# 5VPart.net
KiCad netlist of a schematic drawn in EAGLE
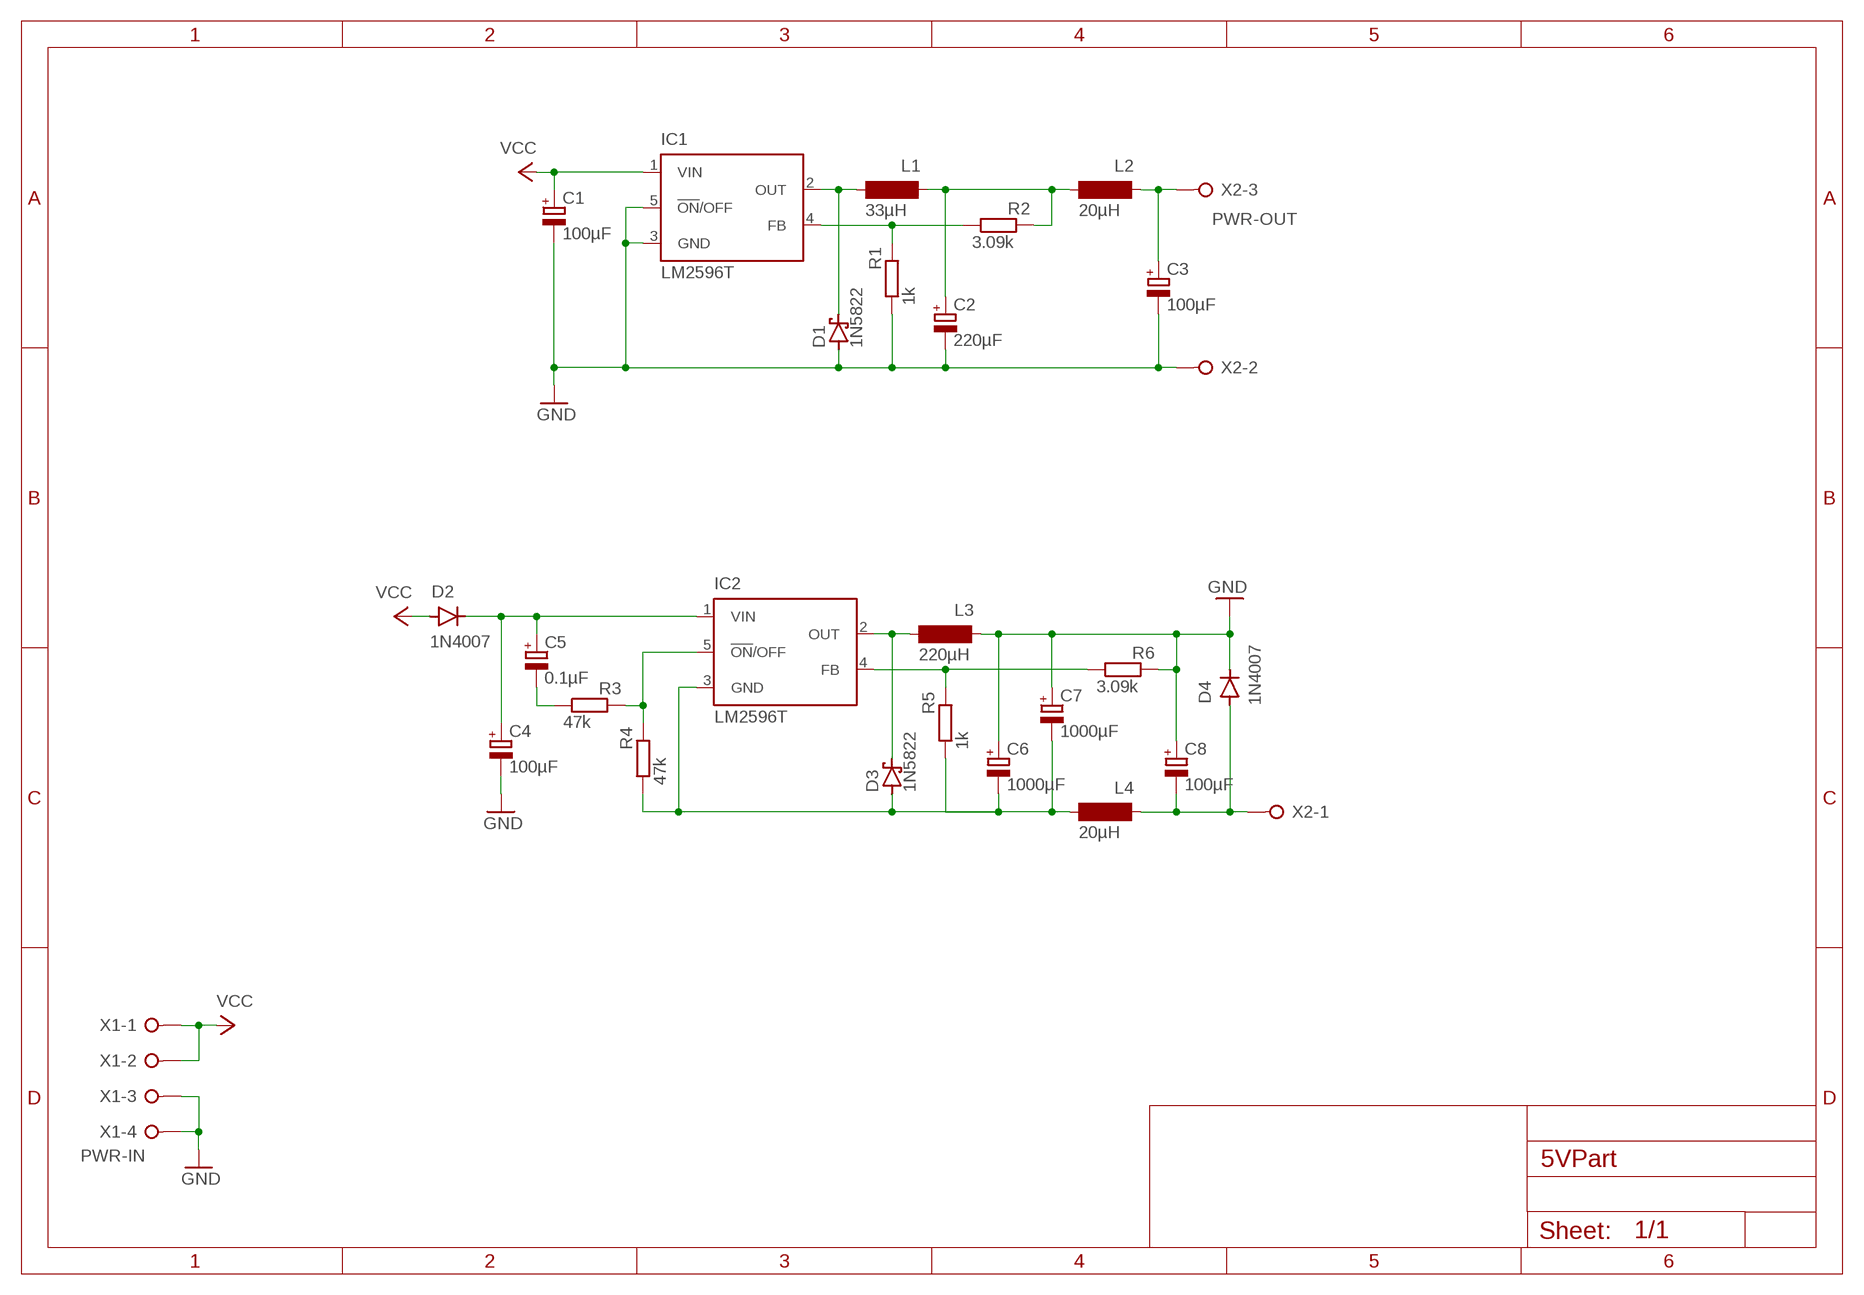
[diagram p0: schematic, sheet 1]

(export (version "E")
  (design (tool "Eeschema 10.0.6"))
  (components
    (comp (ref "C1")
      (value "100µF")
      (footprint "eagle-import:E2,5-6")
      (libsource (lib "eagle-import") (part "CPOL-EUE2.5-6"))
    )
    (comp (ref "C2")
      (value "220µF")
      (footprint "eagle-import:E2,5-6")
      (libsource (lib "eagle-import") (part "CPOL-EUE2.5-6"))
    )
    (comp (ref "C3")
      (value "100µF")
      (footprint "eagle-import:E2,5-6")
      (libsource (lib "eagle-import") (part "CPOL-EUE2.5-6"))
    )
    (comp (ref "C4")
      (value "100µF")
      (footprint "eagle-import:E2,5-6")
      (libsource (lib "eagle-import") (part "CPOL-EUE2.5-6"))
    )
    (comp (ref "C5")
      (value "0.1µF")
      (footprint "eagle-import:E2-4")
      (libsource (lib "eagle-import") (part "CPOL-EUE2-4"))
    )
    (comp (ref "C6")
      (value "1000µF")
      (footprint "eagle-import:E5-10,5")
      (libsource (lib "eagle-import") (part "CPOL-EUE5-10.5"))
    )
    (comp (ref "C7")
      (value "1000µF")
      (footprint "eagle-import:E5-10,5")
      (libsource (lib "eagle-import") (part "CPOL-EUE5-10.5"))
    )
    (comp (ref "C8")
      (value "100µF")
      (footprint "eagle-import:E2,5-6")
      (libsource (lib "eagle-import") (part "CPOL-EUE2.5-6"))
    )
    (comp (ref "D1")
      (value "1N5822")
      (footprint "eagle-import:C4111-15")
      (libsource (lib "eagle-import") (part "1N5908"))
    )
    (comp (ref "D2")
      (value "1N4007")
      (footprint "eagle-import:DO-41")
      (fields
        (field (name "DIGIKEY_PART_NUMBER") "1N4007MSCT-ND")
        (field (name "MANUFACTURER") "Micro Commercial Co")
        (field (name "CREATED_BY") "PCBLayout.com")
      )
      (libsource (lib "eagle-import") (part "1N4007"))
    )
    (comp (ref "D3")
      (value "1N5822")
      (footprint "eagle-import:C4111-15")
      (libsource (lib "eagle-import") (part "1N5908"))
    )
    (comp (ref "D4")
      (value "1N4007")
      (footprint "eagle-import:DO-41")
      (fields
        (field (name "DIGIKEY_PART_NUMBER") "1N4007MSCT-ND")
        (field (name "MANUFACTURER") "Micro Commercial Co")
        (field (name "CREATED_BY") "PCBLayout.com")
      )
      (libsource (lib "eagle-import") (part "1N4007"))
    )
    (comp (ref "IC1")
      (value "LM2596T")
      (footprint "eagle-import:T05D")
      (fields (field (name "MPN") "LM2596T-ADJ/LF02"))
      (libsource (lib "eagle-import") (part "LM2596T"))
    )
    (comp (ref "IC2")
      (value "LM2596T")
      (footprint "eagle-import:T05D")
      (fields (field (name "MPN") "LM2596T-ADJ/LF02"))
      (libsource (lib "eagle-import") (part "LM2596T"))
    )
    (comp (ref "L1")
      (value "33µH")
      (footprint "eagle-import:IND-120")
      (libsource (lib "eagle-import") (part "IND-120-330K"))
    )
    (comp (ref "L2")
      (value "20µH")
      (footprint "eagle-import:B82111B")
      (libsource (lib "eagle-import") (part "B82111B0000C020"))
    )
    (comp (ref "L3")
      (value "220µH")
      (footprint "eagle-import:11PHC")
      (libsource (lib "eagle-import") (part "11PHC-221K-50"))
    )
    (comp (ref "L4")
      (value "20µH")
      (footprint "eagle-import:B82111B")
      (libsource (lib "eagle-import") (part "B82111B0000C020"))
    )
    (comp (ref "R1")
      (value "1k")
      (footprint "eagle-import:0207_10")
      (libsource (lib "eagle-import") (part "R-EU_0207/10"))
    )
    (comp (ref "R2")
      (value "3.09k")
      (footprint "eagle-import:0207_10")
      (libsource (lib "eagle-import") (part "R-EU_0207/10"))
    )
    (comp (ref "R3")
      (value "47k")
      (footprint "eagle-import:0207_10")
      (libsource (lib "eagle-import") (part "R-EU_0207/10"))
    )
    (comp (ref "R4")
      (value "47k")
      (footprint "eagle-import:0207_10")
      (libsource (lib "eagle-import") (part "R-EU_0207/10"))
    )
    (comp (ref "R5")
      (value "1k")
      (footprint "eagle-import:0207_10")
      (libsource (lib "eagle-import") (part "R-EU_0207/10"))
    )
    (comp (ref "R6")
      (value "3.09k")
      (footprint "eagle-import:0207_10")
      (libsource (lib "eagle-import") (part "R-EU_0207/10"))
    )
    (comp (ref "X1")
      (value "PWR-IN")
      (footprint "eagle-import:W237-4P")
      (libsource (lib "eagle-import") (part "W237-04P"))
    )
    (comp (ref "X2")
      (value "PWR-OUT")
      (footprint "eagle-import:W237-133")
      (libsource (lib "eagle-import") (part "W237-03P"))
    )
  )
  (nets
    (net (code "1") (name "GND") (class "Default")
      (node (ref "C1") (pin "-") (pinfunction "-_-") (pintype "passive"))
      (node (ref "C2") (pin "-") (pinfunction "-_-") (pintype "passive"))
      (node (ref "C3") (pin "-") (pinfunction "-_-") (pintype "passive"))
      (node (ref "C4") (pin "-") (pinfunction "-_-") (pintype "passive"))
      (node (ref "C6") (pin "+") (pinfunction "+_+") (pintype "passive"))
      (node (ref "C7") (pin "+") (pinfunction "+_+") (pintype "passive"))
      (node (ref "C8") (pin "+") (pinfunction "+_+") (pintype "passive"))
      (node (ref "D1") (pin "A") (pinfunction "A_A") (pintype "passive"))
      (node (ref "D4") (pin "C") (pinfunction "C_C") (pintype "passive"))
      (node (ref "IC1") (pin "3") (pinfunction "GND_3") (pintype "power_in"))
      (node (ref "IC1") (pin "5") (pinfunction "~{ON}/OFF_5") (pintype "input"))
      (node (ref "L3") (pin "P$2") (pinfunction "2_P$2") (pintype "passive"))
      (node (ref "R1") (pin "1") (pinfunction "1_1") (pintype "passive"))
      (node (ref "R6") (pin "2") (pinfunction "2_2") (pintype "passive"))
      (node (ref "X1") (pin "3") (pinfunction "KL_3") (pintype "passive"))
      (node (ref "X1") (pin "4") (pinfunction "KL_4") (pintype "passive"))
      (node (ref "X2") (pin "2") (pinfunction "KL_2") (pintype "passive"))
    )
    (net (code "2") (name "Net-(C5-Pad-)") (class "Default")
      (node (ref "C5") (pin "-") (pinfunction "-_-") (pintype "passive"))
      (node (ref "R3") (pin "1") (pinfunction "1_1") (pintype "passive"))
    )
    (net (code "3") (name "Net-(IC1-FB)") (class "Default")
      (node (ref "IC1") (pin "4") (pinfunction "FB_4") (pintype "input"))
      (node (ref "R1") (pin "2") (pinfunction "2_2") (pintype "passive"))
      (node (ref "R2") (pin "1") (pinfunction "1_1") (pintype "passive"))
    )
    (net (code "4") (name "Net-(IC1-OUT)") (class "Default")
      (node (ref "D1") (pin "C") (pinfunction "C_C") (pintype "passive"))
      (node (ref "IC1") (pin "2") (pinfunction "OUT_2") (pintype "output"))
      (node (ref "L1") (pin "P$1") (pinfunction "1_P$1") (pintype "passive"))
    )
    (net (code "5") (name "Net-(IC2-FB)") (class "Default")
      (node (ref "IC2") (pin "4") (pinfunction "FB_4") (pintype "input"))
      (node (ref "R5") (pin "2") (pinfunction "2_2") (pintype "passive"))
      (node (ref "R6") (pin "1") (pinfunction "1_1") (pintype "passive"))
    )
    (net (code "6") (name "Net-(IC2-GND)") (class "Default")
      (node (ref "C6") (pin "-") (pinfunction "-_-") (pintype "passive"))
      (node (ref "C7") (pin "-") (pinfunction "-_-") (pintype "passive"))
      (node (ref "D3") (pin "A") (pinfunction "A_A") (pintype "passive"))
      (node (ref "IC2") (pin "3") (pinfunction "GND_3") (pintype "power_in"))
      (node (ref "L4") (pin "P$1") (pinfunction "1_P$1") (pintype "passive"))
      (node (ref "R4") (pin "1") (pinfunction "1_1") (pintype "passive"))
      (node (ref "R5") (pin "1") (pinfunction "1_1") (pintype "passive"))
    )
    (net (code "7") (name "Net-(IC2-OUT)") (class "Default")
      (node (ref "D3") (pin "C") (pinfunction "C_C") (pintype "passive"))
      (node (ref "IC2") (pin "2") (pinfunction "OUT_2") (pintype "output"))
      (node (ref "L3") (pin "P$1") (pinfunction "1_P$1") (pintype "passive"))
    )
    (net (code "8") (name "Net-(IC2-VIN)") (class "Default")
      (node (ref "C4") (pin "+") (pinfunction "+_+") (pintype "passive"))
      (node (ref "C5") (pin "+") (pinfunction "+_+") (pintype "passive"))
      (node (ref "D2") (pin "C") (pinfunction "C_C") (pintype "passive"))
      (node (ref "IC2") (pin "1") (pinfunction "VIN_1") (pintype "input"))
    )
    (net (code "9") (name "Net-(IC2-~{ON}{slash}OFF)") (class "Default")
      (node (ref "IC2") (pin "5") (pinfunction "~{ON}/OFF_5") (pintype "input"))
      (node (ref "R3") (pin "2") (pinfunction "2_2") (pintype "passive"))
      (node (ref "R4") (pin "2") (pinfunction "2_2") (pintype "passive"))
    )
    (net (code "10") (name "Net-(L1-2)") (class "Default")
      (node (ref "C2") (pin "+") (pinfunction "+_+") (pintype "passive"))
      (node (ref "L1") (pin "P$2") (pinfunction "2_P$2") (pintype "passive"))
      (node (ref "L2") (pin "P$1") (pinfunction "1_P$1") (pintype "passive"))
      (node (ref "R2") (pin "2") (pinfunction "2_2") (pintype "passive"))
    )
    (net (code "11") (name "Net-(L2-2)") (class "Default")
      (node (ref "C3") (pin "+") (pinfunction "+_+") (pintype "passive"))
      (node (ref "L2") (pin "P$2") (pinfunction "2_P$2") (pintype "passive"))
      (node (ref "X2") (pin "3") (pinfunction "KL_3") (pintype "passive"))
    )
    (net (code "12") (name "Net-(L4-2)") (class "Default")
      (node (ref "C8") (pin "-") (pinfunction "-_-") (pintype "passive"))
      (node (ref "D4") (pin "A") (pinfunction "A_A") (pintype "passive"))
      (node (ref "L4") (pin "P$2") (pinfunction "2_P$2") (pintype "passive"))
      (node (ref "X2") (pin "1") (pinfunction "KL_1") (pintype "passive"))
    )
    (net (code "13") (name "VCC") (class "Default")
      (node (ref "C1") (pin "+") (pinfunction "+_+") (pintype "passive"))
      (node (ref "D2") (pin "A") (pinfunction "A_A") (pintype "passive"))
      (node (ref "IC1") (pin "1") (pinfunction "VIN_1") (pintype "input"))
      (node (ref "X1") (pin "1") (pinfunction "KL_1") (pintype "passive"))
      (node (ref "X1") (pin "2") (pinfunction "KL_2") (pintype "passive"))
    )
  )
)
